# power.net
KiCad netlist of a schematic drawn in Altium Designer
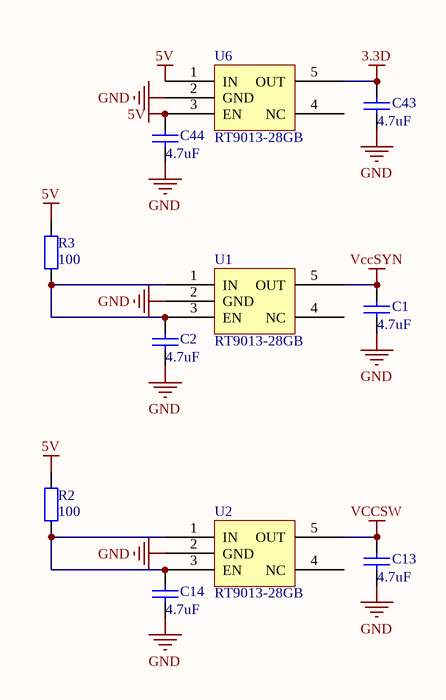
[diagram p0: power.SchDoc]

(export (version "E")
  (design (tool "Eeschema 10.0.6"))
  (components
    (comp (ref "C1")
      (value "4.7uF")
      (footprint "0603")
      (description "Capacitor")
      (fields (field (name "PUBLISHER") "Altium Limited"))
      (libsource (lib "RTC6705") (part "Cap"))
    )
    (comp (ref "C2")
      (value "4.7uF")
      (footprint "0603")
      (description "Capacitor")
      (fields (field (name "PUBLISHER") "Altium Limited"))
      (libsource (lib "RTC6705") (part "Cap"))
    )
    (comp (ref "C13")
      (value "4.7uF")
      (footprint "0603")
      (description "Capacitor")
      (fields (field (name "PUBLISHER") "Altium Limited"))
      (libsource (lib "RTC6705") (part "Cap"))
    )
    (comp (ref "C14")
      (value "4.7uF")
      (footprint "0603")
      (description "Capacitor")
      (fields (field (name "PUBLISHER") "Altium Limited"))
      (libsource (lib "RTC6705") (part "Cap"))
    )
    (comp (ref "C43")
      (value "4.7uF")
      (footprint "0603")
      (description "Capacitor")
      (fields (field (name "PUBLISHER") "Altium Limited"))
      (libsource (lib "RTC6705") (part "Cap"))
    )
    (comp (ref "C44")
      (value "4.7uF")
      (footprint "0603")
      (description "Capacitor")
      (fields (field (name "PUBLISHER") "Altium Limited"))
      (libsource (lib "RTC6705") (part "Cap"))
    )
    (comp (ref "R2")
      (value "100")
      (footprint "0603")
      (description "Resistor")
      (fields (field (name "PUBLISHER") "Altium Limited"))
      (libsource (lib "Miscellaneous Devices") (part "Res2"))
    )
    (comp (ref "R3")
      (value "100")
      (footprint "0603")
      (description "Resistor")
      (fields (field (name "PUBLISHER") "Altium Limited"))
      (libsource (lib "Miscellaneous Devices") (part "Res2"))
    )
    (comp (ref "U1") (value "RT9013-28GB") (footprint "SOT23-5") (libsource (lib "RTC6705") (part "LP5907")))
    (comp (ref "U2") (value "RT9013-28GB") (footprint "SOT23-5") (libsource (lib "RTC6705") (part "LP5907")))
    (comp (ref "U6") (value "RT9013-28GB") (footprint "SOT23-5") (libsource (lib "RTC6705") (part "LP5907")))
  )
  (nets
    (net (code "1") (name "3.3D") (class "Default")
      (node (ref "C43") (pin "2") (pinfunction "2_2") (pintype "passive"))
      (node (ref "U6") (pin "5") (pinfunction "OUT_5") (pintype "passive"))
    )
    (net (code "2") (name "5V") (class "Default")
      (node (ref "C44") (pin "2") (pinfunction "2_2") (pintype "passive"))
      (node (ref "R2") (pin "2") (pinfunction "2_2") (pintype "passive"))
      (node (ref "R3") (pin "2") (pinfunction "2_2") (pintype "passive"))
      (node (ref "U6") (pin "1") (pinfunction "IN_1") (pintype "passive"))
      (node (ref "U6") (pin "3") (pinfunction "EN_3") (pintype "passive"))
    )
    (net (code "3") (name "GND") (class "Default")
      (node (ref "C1") (pin "1") (pinfunction "1_1") (pintype "passive"))
      (node (ref "C13") (pin "1") (pinfunction "1_1") (pintype "passive"))
      (node (ref "C14") (pin "1") (pinfunction "1_1") (pintype "passive"))
      (node (ref "C2") (pin "1") (pinfunction "1_1") (pintype "passive"))
      (node (ref "C43") (pin "1") (pinfunction "1_1") (pintype "passive"))
      (node (ref "C44") (pin "1") (pinfunction "1_1") (pintype "passive"))
      (node (ref "U1") (pin "2") (pinfunction "GND_2") (pintype "passive"))
      (node (ref "U2") (pin "2") (pinfunction "GND_2") (pintype "passive"))
      (node (ref "U6") (pin "2") (pinfunction "GND_2") (pintype "passive"))
    )
    (net (code "4") (name "Net-(U1-EN)") (class "Default")
      (node (ref "C2") (pin "2") (pinfunction "2_2") (pintype "passive"))
      (node (ref "R3") (pin "1") (pinfunction "1_1") (pintype "passive"))
      (node (ref "U1") (pin "1") (pinfunction "IN_1") (pintype "passive"))
      (node (ref "U1") (pin "3") (pinfunction "EN_3") (pintype "passive"))
    )
    (net (code "5") (name "Net-(U2-EN)") (class "Default")
      (node (ref "C14") (pin "2") (pinfunction "2_2") (pintype "passive"))
      (node (ref "R2") (pin "1") (pinfunction "1_1") (pintype "passive"))
      (node (ref "U2") (pin "1") (pinfunction "IN_1") (pintype "passive"))
      (node (ref "U2") (pin "3") (pinfunction "EN_3") (pintype "passive"))
    )
    (net (code "6") (name "VCCSW") (class "Default")
      (node (ref "C13") (pin "2") (pinfunction "2_2") (pintype "passive"))
      (node (ref "U2") (pin "5") (pinfunction "OUT_5") (pintype "passive"))
    )
    (net (code "7") (name "VccSYN") (class "Default")
      (node (ref "C1") (pin "2") (pinfunction "2_2") (pintype "passive"))
      (node (ref "U1") (pin "5") (pinfunction "OUT_5") (pintype "passive"))
    )
    (net (code "8") (name "unconnected-(U1-NC-Pad4)") (class "Default")
      (node (ref "U1") (pin "4") (pinfunction "NC_4") (pintype "passive"))
    )
    (net (code "9") (name "unconnected-(U2-NC-Pad4)") (class "Default")
      (node (ref "U2") (pin "4") (pinfunction "NC_4") (pintype "passive"))
    )
    (net (code "10") (name "unconnected-(U6-NC-Pad4)") (class "Default")
      (node (ref "U6") (pin "4") (pinfunction "NC_4") (pintype "passive"))
    )
  )
)
